# Gyro.net
KiCad netlist of a schematic drawn in Altium Designer
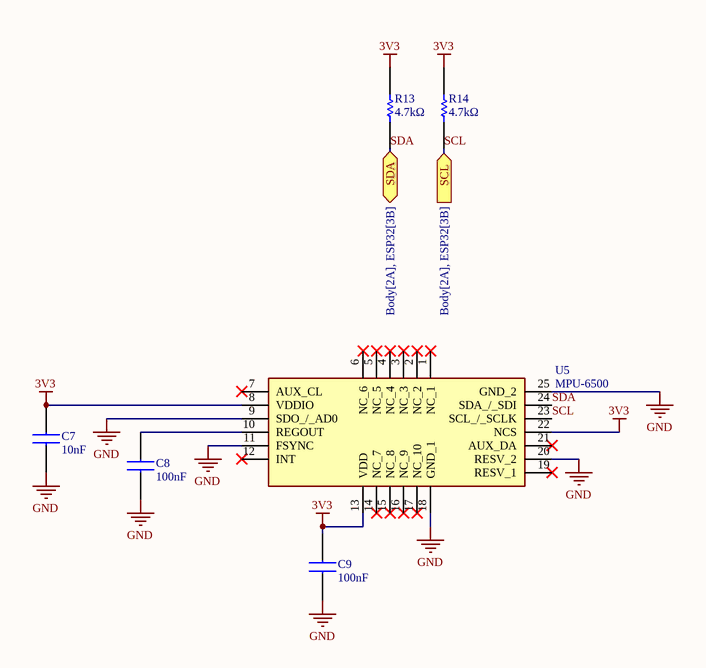
[diagram p0: Gyro.SchDoc]

(export (version "E")
  (design (tool "Eeschema 10.0.6"))
  (components
    (comp (ref "C7")
      (value "10nF")
      (footprint "CAP0805")
      (description "Multilayer Ceramic Capacitors MLCC - SMD/SMT 50 V 10nF X7R 0805 10%")
      (fields (field (name "MANUFACTURER_PART_NUMBER") "CL21B103KBANNNC"))
      (libsource (lib "StandartComponents") (part "CL21B103KBANNNC"))
    )
    (comp (ref "C8")
      (value "100nF")
      (footprint "CAP0805")
      (description "Multilayer Ceramic Capacitors MLCC - SMD/SMT 50 V 0.1uF X7R 0805 10%")
      (fields
        (field (name "MOUSER PART NUMBER") "603-CC805KRX7R9BB104")
        (field (name "MANUFACTURER_PART_NUMBER") "CC0805KRX7R9BB104")
      )
      (libsource (lib "StandartComponents") (part "CC0805KRX7R9BB104"))
    )
    (comp (ref "C9")
      (value "100nF")
      (footprint "CAP0805")
      (description "Multilayer Ceramic Capacitors MLCC - SMD/SMT 50 V 0.1uF X7R 0805 10%")
      (fields
        (field (name "MOUSER PART NUMBER") "603-CC805KRX7R9BB104")
        (field (name "MANUFACTURER_PART_NUMBER") "CC0805KRX7R9BB104")
      )
      (libsource (lib "StandartComponents") (part "CC0805KRX7R9BB104"))
    )
    (comp (ref "R13")
      (value "4.7kΩ")
      (footprint "RES0805")
      (description "125mW Thick Film Resistors 150V ±100ppm/℃ ±1% 4.7kΩ 0805 Chip Resistor - Surface Mount ROHS")
      (fields (field (name "MANUFACTURER_PART_NUMBER") "0805W8F4701T5E"))
      (libsource (lib "StandartComponents") (part "0805W8F4701T5E"))
    )
    (comp (ref "R14")
      (value "4.7kΩ")
      (footprint "RES0805")
      (description "125mW Thick Film Resistors 150V ±100ppm/℃ ±1% 4.7kΩ 0805 Chip Resistor - Surface Mount ROHS")
      (fields (field (name "MANUFACTURER_PART_NUMBER") "0805W8F4701T5E"))
      (libsource (lib "StandartComponents") (part "0805W8F4701T5E"))
    )
    (comp (ref "U5")
      (value "MPU-6500")
      (footprint "QFN-24_L3.0-W3.0-H0.9")
      (description "IMUs - Inertial Measurement Units 6-Axis MEMS MotionTracking  Device with DMP")
      (libsource (lib "MainComponents") (part "MPU-6500"))
    )
  )
  (nets
    (net (code "1") (name "/SCL") (class "Default")
      (node (ref "R14") (pin "1") (pinfunction "1_1") (pintype "passive"))
      (node (ref "U5") (pin "23") (pinfunction "SCL_/_SCLK_23") (pintype "passive"))
    )
    (net (code "2") (name "/SDA") (class "Default")
      (node (ref "R13") (pin "1") (pinfunction "1_1") (pintype "passive"))
      (node (ref "U5") (pin "24") (pinfunction "SDA_/_SDI_24") (pintype "passive"))
    )
    (net (code "3") (name "3V3") (class "Default")
      (node (ref "C7") (pin "1") (pinfunction "1_1") (pintype "passive"))
      (node (ref "C9") (pin "1") (pinfunction "1_1") (pintype "passive"))
      (node (ref "R13") (pin "2") (pinfunction "2_2") (pintype "passive"))
      (node (ref "R14") (pin "2") (pinfunction "2_2") (pintype "passive"))
      (node (ref "U5") (pin "13") (pinfunction "VDD_13") (pintype "passive"))
      (node (ref "U5") (pin "22") (pinfunction "NCS_22") (pintype "passive"))
      (node (ref "U5") (pin "8") (pinfunction "VDDIO_8") (pintype "passive"))
    )
    (net (code "4") (name "GND") (class "Default")
      (node (ref "C7") (pin "2") (pinfunction "2_2") (pintype "passive"))
      (node (ref "C8") (pin "1") (pinfunction "1_1") (pintype "passive"))
      (node (ref "C9") (pin "2") (pinfunction "2_2") (pintype "passive"))
      (node (ref "U5") (pin "11") (pinfunction "FSYNC_11") (pintype "passive"))
      (node (ref "U5") (pin "18") (pinfunction "GND_1_18") (pintype "passive"))
      (node (ref "U5") (pin "20") (pinfunction "RESV_2_20") (pintype "passive"))
      (node (ref "U5") (pin "25") (pinfunction "GND_2_25") (pintype "passive"))
      (node (ref "U5") (pin "9") (pinfunction "SDO_/_AD0_9") (pintype "passive"))
    )
    (net (code "5") (name "Net-(U5-REGOUT)") (class "Default")
      (node (ref "C8") (pin "2") (pinfunction "2_2") (pintype "passive"))
      (node (ref "U5") (pin "10") (pinfunction "REGOUT_10") (pintype "passive"))
    )
    (net (code "6") (name "unconnected-(U5-AUX_CL-Pad7)") (class "Default")
      (node (ref "U5") (pin "7") (pinfunction "AUX_CL_7") (pintype "passive+no_connect"))
    )
    (net (code "7") (name "unconnected-(U5-AUX_DA-Pad21)") (class "Default")
      (node (ref "U5") (pin "21") (pinfunction "AUX_DA_21") (pintype "passive+no_connect"))
    )
    (net (code "8") (name "unconnected-(U5-INT-Pad12)") (class "Default")
      (node (ref "U5") (pin "12") (pinfunction "INT_12") (pintype "passive+no_connect"))
    )
    (net (code "9") (name "unconnected-(U5-NC_1-Pad1)") (class "Default")
      (node (ref "U5") (pin "1") (pinfunction "NC_1_1") (pintype "passive+no_connect"))
    )
    (net (code "10") (name "unconnected-(U5-NC_2-Pad2)") (class "Default")
      (node (ref "U5") (pin "2") (pinfunction "NC_2_2") (pintype "passive+no_connect"))
    )
    (net (code "11") (name "unconnected-(U5-NC_3-Pad3)") (class "Default")
      (node (ref "U5") (pin "3") (pinfunction "NC_3_3") (pintype "passive+no_connect"))
    )
    (net (code "12") (name "unconnected-(U5-NC_4-Pad4)") (class "Default")
      (node (ref "U5") (pin "4") (pinfunction "NC_4_4") (pintype "passive+no_connect"))
    )
    (net (code "13") (name "unconnected-(U5-NC_5-Pad5)") (class "Default")
      (node (ref "U5") (pin "5") (pinfunction "NC_5_5") (pintype "passive+no_connect"))
    )
    (net (code "14") (name "unconnected-(U5-NC_6-Pad6)") (class "Default")
      (node (ref "U5") (pin "6") (pinfunction "NC_6_6") (pintype "passive+no_connect"))
    )
    (net (code "15") (name "unconnected-(U5-NC_7-Pad14)") (class "Default")
      (node (ref "U5") (pin "14") (pinfunction "NC_7_14") (pintype "passive+no_connect"))
    )
    (net (code "16") (name "unconnected-(U5-NC_8-Pad15)") (class "Default")
      (node (ref "U5") (pin "15") (pinfunction "NC_8_15") (pintype "passive+no_connect"))
    )
    (net (code "17") (name "unconnected-(U5-NC_9-Pad16)") (class "Default")
      (node (ref "U5") (pin "16") (pinfunction "NC_9_16") (pintype "passive+no_connect"))
    )
    (net (code "18") (name "unconnected-(U5-NC_10-Pad17)") (class "Default")
      (node (ref "U5") (pin "17") (pinfunction "NC_10_17") (pintype "passive+no_connect"))
    )
    (net (code "19") (name "unconnected-(U5-RESV_1-Pad19)") (class "Default")
      (node (ref "U5") (pin "19") (pinfunction "RESV_1_19") (pintype "passive+no_connect"))
    )
  )
)
